# Main.net
KiCad netlist of a schematic drawn in Altium Designer
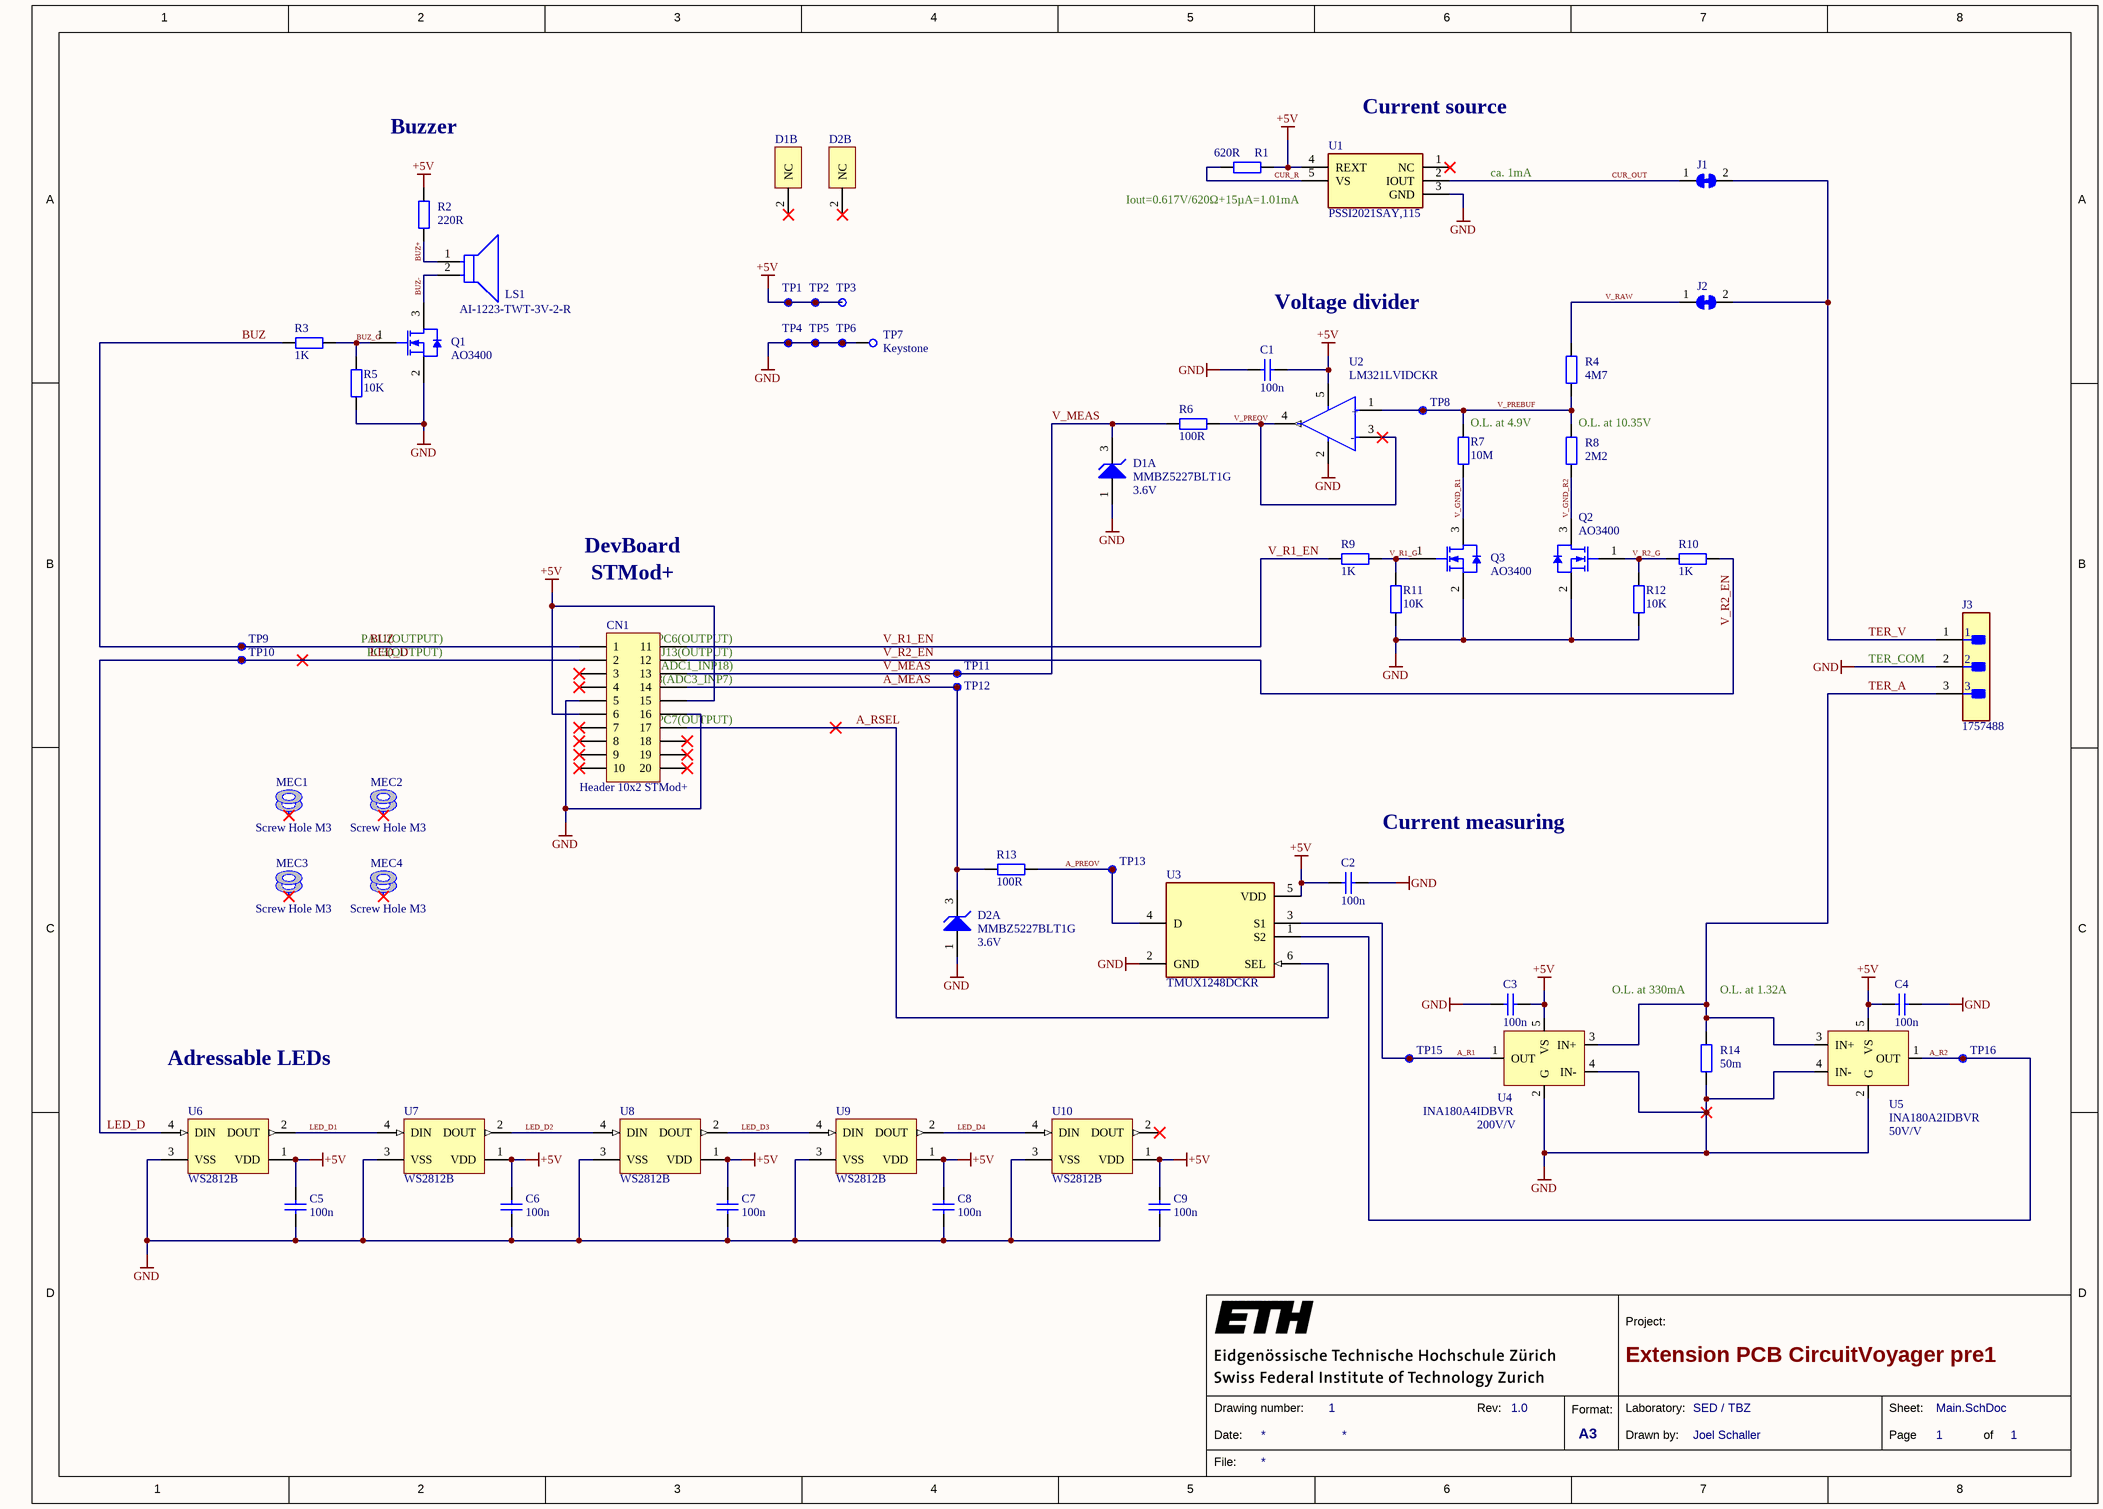
[diagram p0: Main.SchDoc]

(export (version "E")
  (design (tool "Eeschema 10.0.6"))
  (components
    (comp (ref "C1")
      (value "100n")
      (footprint "SMD_CAPC1005X06N")
      (description "CERCAP 100n 16V 5% X7R 0402")
      (fields
        (field (name "MANUFACTURER") "KEMET")
        (field (name "MANUFACTURER PART NUMBER") "C0402C104J4RAC7867")
      )
      (libsource (lib "ETHZ Vault") (part "Cap"))
    )
    (comp (ref "C2")
      (value "100n")
      (footprint "SMD_CAPC1005X06N")
      (description "CERCAP 100n 16V 5% X7R 0402")
      (fields
        (field (name "MANUFACTURER") "KEMET")
        (field (name "MANUFACTURER PART NUMBER") "C0402C104J4RAC7867")
      )
      (libsource (lib "ETHZ Vault") (part "Cap"))
    )
    (comp (ref "C3")
      (value "100n")
      (footprint "SMD_CAPC1005X06N")
      (description "CERCAP 100n 16V 5% X7R 0402")
      (fields
        (field (name "MANUFACTURER") "KEMET")
        (field (name "MANUFACTURER PART NUMBER") "C0402C104J4RAC7867")
      )
      (libsource (lib "ETHZ Vault") (part "Cap"))
    )
    (comp (ref "C4")
      (value "100n")
      (footprint "SMD_CAPC1005X06N")
      (description "CERCAP 100n 16V 5% X7R 0402")
      (fields
        (field (name "MANUFACTURER") "KEMET")
        (field (name "MANUFACTURER PART NUMBER") "C0402C104J4RAC7867")
      )
      (libsource (lib "ETHZ Vault") (part "Cap"))
    )
    (comp (ref "C5")
      (value "100n")
      (footprint "SMD_CAPC1005X06N")
      (description "CERCAP 100n 16V 5% X7R 0402")
      (fields
        (field (name "MANUFACTURER") "KEMET")
        (field (name "MANUFACTURER PART NUMBER") "C0402C104J4RAC7867")
      )
      (libsource (lib "ETHZ Vault") (part "Cap"))
    )
    (comp (ref "C6")
      (value "100n")
      (footprint "SMD_CAPC1005X06N")
      (description "CERCAP 100n 16V 5% X7R 0402")
      (fields
        (field (name "MANUFACTURER") "KEMET")
        (field (name "MANUFACTURER PART NUMBER") "C0402C104J4RAC7867")
      )
      (libsource (lib "ETHZ Vault") (part "Cap"))
    )
    (comp (ref "C7")
      (value "100n")
      (footprint "SMD_CAPC1005X06N")
      (description "CERCAP 100n 16V 5% X7R 0402")
      (fields
        (field (name "MANUFACTURER") "KEMET")
        (field (name "MANUFACTURER PART NUMBER") "C0402C104J4RAC7867")
      )
      (libsource (lib "ETHZ Vault") (part "Cap"))
    )
    (comp (ref "C8")
      (value "100n")
      (footprint "SMD_CAPC1005X06N")
      (description "CERCAP 100n 16V 5% X7R 0402")
      (fields
        (field (name "MANUFACTURER") "KEMET")
        (field (name "MANUFACTURER PART NUMBER") "C0402C104J4RAC7867")
      )
      (libsource (lib "ETHZ Vault") (part "Cap"))
    )
    (comp (ref "C9")
      (value "100n")
      (footprint "SMD_CAPC1005X06N")
      (description "CERCAP 100n 16V 5% X7R 0402")
      (fields
        (field (name "MANUFACTURER") "KEMET")
        (field (name "MANUFACTURER PART NUMBER") "C0402C104J4RAC7867")
      )
      (libsource (lib "ETHZ Vault") (part "Cap"))
    )
    (comp (ref "CN1")
      (value "Header 10x2 STMod+")
      (footprint "MB1280:CON_SAMTEC_TMM-110-01-L-D-RA__STMOD+")
      (description "Header 10x2, 2mm, RA, TH, Height 3.20mm/3.50mm,BF060-20A-B-0400-0280-0305-L-D")
      (fields
        (field (name "INTERNAL_PART_NUMBER") "MCD-00288")
        (field (name "MANUFACTURER_PART_NUMBER") "TMM-110-01-L-D-RA")
        (field (name "PROVIDED_BY") "SUBCO")
      )
      (libsource (lib "MCD_PARTS_database") (part "Header 10x2 STMod+"))
    )
    (comp (ref "D1")
      (value "MMBZ5227BLT1G")
      (footprint "ONSC-SOT-23-3-318-08_V")
      (description "Zener Voltage Regulator, 225 mW, 3-Pin SOT-23, Pb-Free, Tape and Reel")
      (fields (field (name "VZ TYP (V)") "3.6V") (field (name "MANUFACTURER") "On Semiconductor"))
      (libsource (lib "Altium Content Vault") (part "ONSC-A1K3-3"))
    )
    (comp (ref "D2")
      (value "MMBZ5227BLT1G")
      (footprint "ONSC-SOT-23-3-318-08_V")
      (description "Zener Voltage Regulator, 225 mW, 3-Pin SOT-23, Pb-Free, Tape and Reel")
      (fields (field (name "VZ TYP (V)") "3.6V") (field (name "MANUFACTURER") "On Semiconductor"))
      (libsource (lib "Altium Content Vault") (part "ONSC-A1K3-3"))
    )
    (comp (ref "J1")
      (value "SOLDERJUMPER_CLOSED_1MM")
      (footprint "SOLDERBRIDGE_CLOSED_1MM")
      (description "TP SOLDERJUMPER CLOSED 1mm")
      (libsource (lib "ETHZ Vault") (part "CON SOLDER JUMPER CLOSED"))
    )
    (comp (ref "J2")
      (value "SOLDERJUMPER_CLOSED_1MM")
      (footprint "SOLDERBRIDGE_CLOSED_1MM")
      (description "TP SOLDERJUMPER CLOSED 1mm")
      (libsource (lib "ETHZ Vault") (part "CON SOLDER JUMPER CLOSED"))
    )
    (comp (ref "J3")
      (value "1757488")
      (footprint "FP-1757488-MFG")
      (description "TERM BLOCK HDR 3POS 90DEG 5MM")
      (fields
        (field (name "OCTOPART") "https://octopart.com/1757488-phoenix+contact-37691")
        (field (name "MANUFACTURER") "Phoenix Contact")
      )
      (libsource (lib "Altium Content Vault") (part "0d3f023dd272f625e17a2be33dea85f"))
    )
    (comp (ref "LS1")
      (value "AI-1223-TWT-3V-2-R")
      (footprint "FP-AI-1223-TWT-3V-2-R-MFG")
      (description "BUZZER MAGNETIC 3V 12MM TH")
      (libsource (lib "Altium Content Vault") (part "1973c4b650225fd2ddacaff6b763965"))
    )
    (comp (ref "MEC1")
      (value "Screw Hole M3")
      (footprint "Screw M3 ISO 7380-1")
      (description "EMECH Generic Screw Hole - different sizes")
      (libsource (lib "ETHZ Vault") (part "Generic Screw Hole"))
    )
    (comp (ref "MEC2")
      (value "Screw Hole M3")
      (footprint "Screw M3 ISO 7380-1")
      (description "EMECH Generic Screw Hole - different sizes")
      (libsource (lib "ETHZ Vault") (part "Generic Screw Hole"))
    )
    (comp (ref "MEC3")
      (value "Screw Hole M3")
      (footprint "Screw M3 ISO 7380-1")
      (description "EMECH Generic Screw Hole - different sizes")
      (libsource (lib "ETHZ Vault") (part "Generic Screw Hole"))
    )
    (comp (ref "MEC4")
      (value "Screw Hole M3")
      (footprint "Screw M3 ISO 7380-1")
      (description "EMECH Generic Screw Hole - different sizes")
      (libsource (lib "ETHZ Vault") (part "Generic Screw Hole"))
    )
    (comp (ref "Q1")
      (value "AO3400")
      (footprint "AO-SOT23-3_V")
      (description "N-channel Enhancement Mode Field-Effect Transistor; 5.8A/30V")
      (fields (field (name "MANUFACTURER") "Alpha and Omega"))
      (libsource (lib "Altium Content Vault") (part "AO-NEMOS-G1S2D3-3"))
    )
    (comp (ref "Q2")
      (value "AO3400")
      (footprint "AO-SOT23-3_V")
      (description "N-channel Enhancement Mode Field-Effect Transistor; 5.8A/30V")
      (fields (field (name "MANUFACTURER") "Alpha and Omega"))
      (libsource (lib "Altium Content Vault") (part "AO-NEMOS-G1S2D3-3"))
    )
    (comp (ref "Q3")
      (value "AO3400")
      (footprint "AO-SOT23-3_V")
      (description "N-channel Enhancement Mode Field-Effect Transistor; 5.8A/30V")
      (fields (field (name "MANUFACTURER") "Alpha and Omega"))
      (libsource (lib "Altium Content Vault") (part "AO-NEMOS-G1S2D3-3"))
    )
    (comp (ref "R1")
      (value "620R")
      (footprint "SMD_RESC1005X04N")
      (description "RES 620R 62.5mW 1% 0402")
      (fields
        (field (name "MANUFACTURER") "YAEGO")
        (field (name "MANUFACTURER PART NUMBER") "RC0402FR-07620RL")
      )
      (libsource (lib "ETHZ Vault") (part "Res"))
    )
    (comp (ref "R2")
      (value "220R")
      (footprint "SMD_RESC1005X04N")
      (description "RES 220R 62.5mW 1% 0402")
      (fields
        (field (name "MANUFACTURER") "YAEGO")
        (field (name "MANUFACTURER PART NUMBER") "RC0402FR-07220RL")
      )
      (libsource (lib "ETHZ Vault") (part "Res"))
    )
    (comp (ref "R3")
      (value "1K")
      (footprint "SMD_RESC1005X04N")
      (description "RES 1K 62.5mW 1% 0402")
      (fields
        (field (name "MANUFACTURER") "YAEGO")
        (field (name "MANUFACTURER PART NUMBER") "RC0402FR-071KL")
      )
      (libsource (lib "ETHZ Vault") (part "Res"))
    )
    (comp (ref "R4")
      (value "4M7")
      (footprint "SMD_RESC1005X04N")
      (description "RES 4M7 62.5mW 1% 0402")
      (fields
        (field (name "MANUFACTURER") "YAEGO")
        (field (name "MANUFACTURER PART NUMBER") "RC0402FR-074M7L")
      )
      (libsource (lib "ETHZ Vault") (part "Res"))
    )
    (comp (ref "R5")
      (value "10K")
      (footprint "SMD_RESC1005X04N")
      (description "RES 10K 62.5mW 1% 0402")
      (fields
        (field (name "MANUFACTURER") "YAEGO")
        (field (name "MANUFACTURER PART NUMBER") "RC0402FR-0710KL")
      )
      (libsource (lib "ETHZ Vault") (part "Res"))
    )
    (comp (ref "R6")
      (value "100R")
      (footprint "SMD_RESC1005X04N")
      (description "RES 100R 62.5mW 1% 0402")
      (fields
        (field (name "MANUFACTURER") "YAEGO")
        (field (name "MANUFACTURER PART NUMBER") "RC0402FR-07100RL")
      )
      (libsource (lib "ETHZ Vault") (part "Res"))
    )
    (comp (ref "R7")
      (value "10M")
      (footprint "SMD_RESC1005X04N")
      (description "RES 10M 62.5mW 1% 0402")
      (fields
        (field (name "MANUFACTURER") "YAEGO")
        (field (name "MANUFACTURER PART NUMBER") "RC0402FR-0710ML")
      )
      (libsource (lib "ETHZ Vault") (part "Res"))
    )
    (comp (ref "R8")
      (value "2M2")
      (footprint "SMD_RESC1005X04N")
      (description "RES 2M2 62.5mW 1% 0402")
      (fields
        (field (name "MANUFACTURER") "YAEGO")
        (field (name "MANUFACTURER PART NUMBER") "RC0402FR-072M2L")
      )
      (libsource (lib "ETHZ Vault") (part "Res"))
    )
    (comp (ref "R9")
      (value "1K")
      (footprint "SMD_RESC1005X04N")
      (description "RES 1K 62.5mW 1% 0402")
      (fields
        (field (name "MANUFACTURER") "YAEGO")
        (field (name "MANUFACTURER PART NUMBER") "RC0402FR-071KL")
      )
      (libsource (lib "ETHZ Vault") (part "Res"))
    )
    (comp (ref "R10")
      (value "1K")
      (footprint "SMD_RESC1005X04N")
      (description "RES 1K 62.5mW 1% 0402")
      (fields
        (field (name "MANUFACTURER") "YAEGO")
        (field (name "MANUFACTURER PART NUMBER") "RC0402FR-071KL")
      )
      (libsource (lib "ETHZ Vault") (part "Res"))
    )
    (comp (ref "R11")
      (value "10K")
      (footprint "SMD_RESC1005X04N")
      (description "RES 10K 62.5mW 1% 0402")
      (fields
        (field (name "MANUFACTURER") "YAEGO")
        (field (name "MANUFACTURER PART NUMBER") "RC0402FR-0710KL")
      )
      (libsource (lib "ETHZ Vault") (part "Res"))
    )
    (comp (ref "R12")
      (value "10K")
      (footprint "SMD_RESC1005X04N")
      (description "RES 10K 62.5mW 1% 0402")
      (fields
        (field (name "MANUFACTURER") "YAEGO")
        (field (name "MANUFACTURER PART NUMBER") "RC0402FR-0710KL")
      )
      (libsource (lib "ETHZ Vault") (part "Res"))
    )
    (comp (ref "R13")
      (value "100R")
      (footprint "SMD_RESC1005X04N")
      (description "RES 100R 62.5mW 1% 0402")
      (fields
        (field (name "MANUFACTURER") "YAEGO")
        (field (name "MANUFACTURER PART NUMBER") "RC0402FR-07100RL")
      )
      (libsource (lib "ETHZ Vault") (part "Res"))
    )
    (comp (ref "R14")
      (value "50m")
      (footprint "SMD_RESC2012X05N")
      (description "RES 0R05 125mW 1% 0805")
      (fields (field (name "Comment") "R0805"))
      (libsource (lib "ETHZ Vault") (part "Res"))
    )
    (comp (ref "TP1")
      (value "Test Point Small")
      (footprint "SMD_PAD_1mm")
      (description "TP TESTPOINT MULTIPLE_SIZE")
      (libsource (lib "ETHZ Vault") (part "Test Point Small"))
    )
    (comp (ref "TP2")
      (value "Test Point Small")
      (footprint "SMD_PAD_1mm")
      (description "TP TESTPOINT MULTIPLE_SIZE")
      (libsource (lib "ETHZ Vault") (part "Test Point Small"))
    )
    (comp (ref "TP3")
      (value "Test Point Small")
      (footprint "SMD_PAD_1mm")
      (description "TP TESTPOINT MULTIPLE_SIZE")
      (libsource (lib "ETHZ Vault") (part "Test Point Small"))
    )
    (comp (ref "TP4")
      (value "Test Point Small")
      (footprint "SMD_PAD_1mm")
      (description "TP TESTPOINT MULTIPLE_SIZE")
      (libsource (lib "ETHZ Vault") (part "Test Point Small"))
    )
    (comp (ref "TP5")
      (value "Test Point Small")
      (footprint "SMD_PAD_1mm")
      (description "TP TESTPOINT MULTIPLE_SIZE")
      (libsource (lib "ETHZ Vault") (part "Test Point Small"))
    )
    (comp (ref "TP6")
      (value "Test Point Small")
      (footprint "SMD_PAD_1mm")
      (description "TP TESTPOINT MULTIPLE_SIZE")
      (libsource (lib "ETHZ Vault") (part "Test Point Small"))
    )
    (comp (ref "TP7")
      (value "Keystone")
      (footprint "KEYSTONE_5019")
      (description "TP SMD 3.81x 2.03mm")
      (fields
        (field (name "MANUFACTURER") "Keystone Electronics")
        (field (name "MANUFACTURER PART NUMBER") "5019")
      )
      (libsource (lib "ETHZ Vault") (part "Test Point"))
    )
    (comp (ref "TP8")
      (value "Test Point Small")
      (footprint "SMD_PAD_1mm")
      (description "TP TESTPOINT MULTIPLE_SIZE")
      (libsource (lib "ETHZ Vault") (part "Test Point Small"))
    )
    (comp (ref "TP9")
      (value "Test Point Small")
      (footprint "SMD_PAD_1mm")
      (description "TP TESTPOINT MULTIPLE_SIZE")
      (libsource (lib "ETHZ Vault") (part "Test Point Small"))
    )
    (comp (ref "TP10")
      (value "Test Point Small")
      (footprint "SMD_PAD_1mm")
      (description "TP TESTPOINT MULTIPLE_SIZE")
      (libsource (lib "ETHZ Vault") (part "Test Point Small"))
    )
    (comp (ref "TP11")
      (value "Test Point Small")
      (footprint "SMD_PAD_1mm")
      (description "TP TESTPOINT MULTIPLE_SIZE")
      (libsource (lib "ETHZ Vault") (part "Test Point Small"))
    )
    (comp (ref "TP12")
      (value "Test Point Small")
      (footprint "SMD_PAD_1mm")
      (description "TP TESTPOINT MULTIPLE_SIZE")
      (libsource (lib "ETHZ Vault") (part "Test Point Small"))
    )
    (comp (ref "TP13")
      (value "Test Point Small")
      (footprint "SMD_PAD_1mm")
      (description "TP TESTPOINT MULTIPLE_SIZE")
      (libsource (lib "ETHZ Vault") (part "Test Point Small"))
    )
    (comp (ref "TP15")
      (value "Test Point Small")
      (footprint "SMD_PAD_1mm")
      (description "TP TESTPOINT MULTIPLE_SIZE")
      (libsource (lib "ETHZ Vault") (part "Test Point Small"))
    )
    (comp (ref "TP16")
      (value "Test Point Small")
      (footprint "SMD_PAD_1mm")
      (description "TP TESTPOINT MULTIPLE_SIZE")
      (libsource (lib "ETHZ Vault") (part "Test Point Small"))
    )
    (comp (ref "U1")
      (value "PSSI2021SAY,115")
      (footprint "SOT65P210X100-5N:SOT65P210X100-5N")
      (description "NEXPERIA - PSSI2021SAY,115 - IC, CURRENT SOURCE, 50MA, 75V,SOT353")
      (fields (field (name "MOUSER PART NUMBER") "771-PSSI2021SAY-T/R"))
      (libsource (lib "PSSI2021SAY_115") (part "PSSI2021SAY_115"))
    )
    (comp (ref "U2")
      (value "LM321LVIDCKR")
      (footprint "FP-DCK0005A-IPC_B")
      (description "IC OPAMP GP 1 CIRCUIT SC70-5")
      (libsource (lib "Altium Content Vault") (part "471d8b929410cd356ad4b122f572ce5"))
    )
    (comp (ref "U3")
      (value "TMUX1248DCKR")
      (footprint "FP-DCK0006A-IPC_B")
      (description "3- LOW RON, 5-V, 2:1 (SPDT) GENE")
      (libsource (lib "Altium Content Vault") (part "a68f7588cd528286686894cb26da2a0"))
    )
    (comp (ref "U4")
      (value "INA180A4IDBVR")
      (footprint "FP-DBV0005A-IPC_B")
      (description "Operational Amplifier, 1 Func, 500uV Offset-Max, PDSO5")
      (fields (field (name "ALTIUM_VALUE") "200V/V"))
      (libsource (lib "Joel's WS") (part "0a55cf1a948ad01a3239aec1b7efad0"))
    )
    (comp (ref "U5")
      (value "INA180A2IDBVR")
      (footprint "FP-DBV0005A-IPC_B")
      (description "Operational Amplifier, 1 Func, 500uV Offset-Max, PDSO5")
      (fields (field (name "ALTIUM_VALUE") "50V/V"))
      (libsource (lib "") (part "0a55cf1a948ad01a3239aec1b7efad0_1"))
    )
    (comp (ref "U6")
      (value "WS2812B")
      (footprint "ADAI-WS2812B_V")
      (fields (field (name "MANUFACTURER") "Adafruit Industries"))
      (libsource (lib "ETH Zürich") (part "ADAI-WS2812B-4"))
    )
    (comp (ref "U7")
      (value "WS2812B")
      (footprint "ADAI-WS2812B_V")
      (fields (field (name "MANUFACTURER") "Adafruit Industries"))
      (libsource (lib "ETH Zürich") (part "ADAI-WS2812B-4"))
    )
    (comp (ref "U8")
      (value "WS2812B")
      (footprint "ADAI-WS2812B_V")
      (fields (field (name "MANUFACTURER") "Adafruit Industries"))
      (libsource (lib "ETH Zürich") (part "ADAI-WS2812B-4"))
    )
    (comp (ref "U9")
      (value "WS2812B")
      (footprint "ADAI-WS2812B_V")
      (fields (field (name "MANUFACTURER") "Adafruit Industries"))
      (libsource (lib "ETH Zürich") (part "ADAI-WS2812B-4"))
    )
    (comp (ref "U10")
      (value "WS2812B")
      (footprint "ADAI-WS2812B_V")
      (fields (field (name "MANUFACTURER") "Adafruit Industries"))
      (libsource (lib "ETH Zürich") (part "ADAI-WS2812B-4"))
    )
  )
  (nets
    (net (code "1") (name "+5V") (class "Default")
      (node (ref "C1") (pin "1") (pinfunction "1_1") (pintype "passive"))
      (node (ref "C2") (pin "1") (pinfunction "1_1") (pintype "passive"))
      (node (ref "C3") (pin "1") (pinfunction "1_1") (pintype "passive"))
      (node (ref "C4") (pin "1") (pinfunction "1_1") (pintype "passive"))
      (node (ref "C5") (pin "2") (pinfunction "2_2") (pintype "passive"))
      (node (ref "C6") (pin "2") (pinfunction "2_2") (pintype "passive"))
      (node (ref "C7") (pin "2") (pinfunction "2_2") (pintype "passive"))
      (node (ref "C8") (pin "2") (pinfunction "2_2") (pintype "passive"))
      (node (ref "C9") (pin "2") (pinfunction "2_2") (pintype "passive"))
      (node (ref "CN1") (pin "15") (pinfunction "15_15") (pintype "passive"))
      (node (ref "CN1") (pin "6") (pinfunction "6_6") (pintype "passive"))
      (node (ref "R1") (pin "1") (pinfunction "1_1") (pintype "passive"))
      (node (ref "R2") (pin "2") (pinfunction "2_2") (pintype "passive"))
      (node (ref "TP1") (pin "1") (pinfunction "1_1") (pintype "passive"))
      (node (ref "TP2") (pin "1") (pinfunction "1_1") (pintype "passive"))
      (node (ref "TP3") (pin "1") (pinfunction "1_1") (pintype "passive"))
      (node (ref "U1") (pin "4") (pinfunction "REXT_4") (pintype "passive"))
      (node (ref "U10") (pin "1") (pinfunction "VDD_1") (pintype "power_in"))
      (node (ref "U2") (pin "5") (pinfunction "V+_5") (pintype "power_in"))
      (node (ref "U3") (pin "5") (pinfunction "VDD_5") (pintype "power_in"))
      (node (ref "U4") (pin "5") (pinfunction "VS_5") (pintype "power_in"))
      (node (ref "U5") (pin "5") (pinfunction "VS_5") (pintype "power_in"))
      (node (ref "U6") (pin "1") (pinfunction "VDD_1") (pintype "power_in"))
      (node (ref "U7") (pin "1") (pinfunction "VDD_1") (pintype "power_in"))
      (node (ref "U8") (pin "1") (pinfunction "VDD_1") (pintype "power_in"))
      (node (ref "U9") (pin "1") (pinfunction "VDD_1") (pintype "power_in"))
    )
    (net (code "2") (name "/A_MEAS") (class "Default")
      (node (ref "CN1") (pin "14") (pinfunction "14_14") (pintype "passive"))
      (node (ref "D2") (pin "3") (pinfunction "K_3") (pintype "passive"))
      (node (ref "R13") (pin "1") (pinfunction "1_1") (pintype "passive"))
      (node (ref "TP12") (pin "1") (pinfunction "1_1") (pintype "passive"))
    )
    (net (code "3") (name "/A_PREOV") (class "Default")
      (node (ref "R13") (pin "2") (pinfunction "2_2") (pintype "passive"))
      (node (ref "TP13") (pin "1") (pinfunction "1_1") (pintype "passive"))
      (node (ref "U3") (pin "4") (pinfunction "D_4") (pintype "passive"))
    )
    (net (code "4") (name "/A_R1") (class "Default")
      (node (ref "TP15") (pin "1") (pinfunction "1_1") (pintype "passive"))
      (node (ref "U3") (pin "3") (pinfunction "S1_3") (pintype "passive"))
      (node (ref "U4") (pin "1") (pinfunction "OUT_1") (pintype "passive"))
    )
    (net (code "5") (name "/A_R2") (class "Default")
      (node (ref "TP16") (pin "1") (pinfunction "1_1") (pintype "passive"))
      (node (ref "U3") (pin "1") (pinfunction "S2_1") (pintype "passive"))
      (node (ref "U5") (pin "1") (pinfunction "OUT_1") (pintype "passive"))
    )
    (net (code "6") (name "/A_RSEL") (class "Default")
      (node (ref "CN1") (pin "17") (pinfunction "17_17") (pintype "passive"))
      (node (ref "U3") (pin "6") (pinfunction "SEL_6") (pintype "input"))
    )
    (net (code "7") (name "/BUZ") (class "Default")
      (node (ref "CN1") (pin "1") (pinfunction "1_1") (pintype "passive"))
      (node (ref "R3") (pin "2") (pinfunction "2_2") (pintype "passive"))
      (node (ref "TP9") (pin "1") (pinfunction "1_1") (pintype "passive"))
    )
    (net (code "8") (name "/BUZ+") (class "Default")
      (node (ref "LS1") (pin "1") (pinfunction "C_1") (pintype "passive"))
      (node (ref "R2") (pin "1") (pinfunction "1_1") (pintype "passive"))
    )
    (net (code "9") (name "/BUZ-") (class "Default")
      (node (ref "LS1") (pin "2") (pinfunction "A_2") (pintype "passive"))
      (node (ref "Q1") (pin "3") (pinfunction "D_3") (pintype "passive"))
    )
    (net (code "10") (name "/BUZ_G") (class "Default")
      (node (ref "Q1") (pin "1") (pinfunction "G_1") (pintype "passive"))
      (node (ref "R3") (pin "1") (pinfunction "1_1") (pintype "passive"))
      (node (ref "R5") (pin "2") (pinfunction "2_2") (pintype "passive"))
    )
    (net (code "11") (name "/CUR_OUT") (class "Default")
      (node (ref "J1") (pin "1") (pinfunction "1_1") (pintype "passive"))
      (node (ref "U1") (pin "2") (pinfunction "IOUT_2") (pintype "passive"))
    )
    (net (code "12") (name "/CUR_R") (class "Default")
      (node (ref "R1") (pin "2") (pinfunction "2_2") (pintype "passive"))
      (node (ref "U1") (pin "5") (pinfunction "VS_5") (pintype "power_in"))
    )
    (net (code "13") (name "/LED_D") (class "Default")
      (node (ref "CN1") (pin "2") (pinfunction "2_2") (pintype "passive"))
      (node (ref "TP10") (pin "1") (pinfunction "1_1") (pintype "passive"))
      (node (ref "U6") (pin "4") (pinfunction "DIN_4") (pintype "input"))
    )
    (net (code "14") (name "/LED_D1") (class "Default")
      (node (ref "U6") (pin "2") (pinfunction "DOUT_2") (pintype "output"))
      (node (ref "U7") (pin "4") (pinfunction "DIN_4") (pintype "input"))
    )
    (net (code "15") (name "/LED_D2") (class "Default")
      (node (ref "U7") (pin "2") (pinfunction "DOUT_2") (pintype "output"))
      (node (ref "U8") (pin "4") (pinfunction "DIN_4") (pintype "input"))
    )
    (net (code "16") (name "/LED_D3") (class "Default")
      (node (ref "U8") (pin "2") (pinfunction "DOUT_2") (pintype "output"))
      (node (ref "U9") (pin "4") (pinfunction "DIN_4") (pintype "input"))
    )
    (net (code "17") (name "/LED_D4") (class "Default")
      (node (ref "U10") (pin "4") (pinfunction "DIN_4") (pintype "input"))
      (node (ref "U9") (pin "2") (pinfunction "DOUT_2") (pintype "output"))
    )
    (net (code "18") (name "/TER_A") (class "Default")
      (node (ref "J3") (pin "3") (pinfunction "3_3") (pintype "passive"))
      (node (ref "R14") (pin "2") (pinfunction "2_2") (pintype "passive"))
      (node (ref "U4") (pin "3") (pinfunction "IN+_3") (pintype "tri_state"))
      (node (ref "U5") (pin "3") (pinfunction "IN+_3") (pintype "tri_state"))
    )
    (net (code "19") (name "/TER_V") (class "Default")
      (node (ref "J1") (pin "2") (pinfunction "2_2") (pintype "passive"))
      (node (ref "J2") (pin "2") (pinfunction "2_2") (pintype "passive"))
      (node (ref "J3") (pin "1") (pinfunction "1_1") (pintype "passive"))
    )
    (net (code "20") (name "/V_GND_R1") (class "Default")
      (node (ref "Q3") (pin "3") (pinfunction "D_3") (pintype "passive"))
      (node (ref "R7") (pin "1") (pinfunction "1_1") (pintype "passive"))
    )
    (net (code "21") (name "/V_GND_R2") (class "Default")
      (node (ref "Q2") (pin "3") (pinfunction "D_3") (pintype "passive"))
      (node (ref "R8") (pin "1") (pinfunction "1_1") (pintype "passive"))
    )
    (net (code "22") (name "/V_MEAS") (class "Default")
      (node (ref "CN1") (pin "13") (pinfunction "13_13") (pintype "passive"))
      (node (ref "D1") (pin "3") (pinfunction "K_3") (pintype "passive"))
      (node (ref "R6") (pin "1") (pinfunction "1_1") (pintype "passive"))
      (node (ref "TP11") (pin "1") (pinfunction "1_1") (pintype "passive"))
    )
    (net (code "23") (name "/V_PREBUF") (class "Default")
      (node (ref "R4") (pin "1") (pinfunction "1_1") (pintype "passive"))
      (node (ref "R7") (pin "2") (pinfunction "2_2") (pintype "passive"))
      (node (ref "R8") (pin "2") (pinfunction "2_2") (pintype "passive"))
      (node (ref "TP8") (pin "1") (pinfunction "1_1") (pintype "passive"))
      (node (ref "U2") (pin "1") (pinfunction "IN+_1") (pintype "tri_state"))
    )
    (net (code "24") (name "/V_PREOV") (class "Default")
      (node (ref "R6") (pin "2") (pinfunction "2_2") (pintype "passive"))
      (node (ref "U2") (pin "3") (pinfunction "IN-_3") (pintype "tri_state"))
      (node (ref "U2") (pin "4") (pinfunction "OUT_4") (pintype "output"))
    )
    (net (code "25") (name "/V_R1_EN") (class "Default")
      (node (ref "CN1") (pin "11") (pinfunction "11_11") (pintype "passive"))
      (node (ref "R9") (pin "2") (pinfunction "2_2") (pintype "passive"))
    )
    (net (code "26") (name "/V_R1_G") (class "Default")
      (node (ref "Q3") (pin "1") (pinfunction "G_1") (pintype "passive"))
      (node (ref "R11") (pin "2") (pinfunction "2_2") (pintype "passive"))
      (node (ref "R9") (pin "1") (pinfunction "1_1") (pintype "passive"))
    )
    (net (code "27") (name "/V_R2_EN") (class "Default")
      (node (ref "CN1") (pin "12") (pinfunction "12_12") (pintype "passive"))
      (node (ref "R10") (pin "2") (pinfunction "2_2") (pintype "passive"))
    )
    (net (code "28") (name "/V_R2_G") (class "Default")
      (node (ref "Q2") (pin "1") (pinfunction "G_1") (pintype "passive"))
      (node (ref "R10") (pin "1") (pinfunction "1_1") (pintype "passive"))
      (node (ref "R12") (pin "2") (pinfunction "2_2") (pintype "passive"))
    )
    (net (code "29") (name "/V_RAW") (class "Default")
      (node (ref "J2") (pin "1") (pinfunction "1_1") (pintype "passive"))
      (node (ref "R4") (pin "2") (pinfunction "2_2") (pintype "passive"))
    )
    (net (code "30") (name "GND") (class "Default")
      (node (ref "C1") (pin "2") (pinfunction "2_2") (pintype "passive"))
      (node (ref "C2") (pin "2") (pinfunction "2_2") (pintype "passive"))
      (node (ref "C3") (pin "2") (pinfunction "2_2") (pintype "passive"))
      (node (ref "C4") (pin "2") (pinfunction "2_2") (pintype "passive"))
      (node (ref "C5") (pin "1") (pinfunction "1_1") (pintype "passive"))
      (node (ref "C6") (pin "1") (pinfunction "1_1") (pintype "passive"))
      (node (ref "C7") (pin "1") (pinfunction "1_1") (pintype "passive"))
      (node (ref "C8") (pin "1") (pinfunction "1_1") (pintype "passive"))
      (node (ref "C9") (pin "1") (pinfunction "1_1") (pintype "passive"))
      (node (ref "CN1") (pin "16") (pinfunction "16_16") (pintype "passive"))
      (node (ref "CN1") (pin "5") (pinfunction "5_5") (pintype "passive"))
      (node (ref "D1") (pin "1") (pinfunction "A_1") (pintype "passive"))
      (node (ref "D2") (pin "1") (pinfunction "A_1") (pintype "passive"))
      (node (ref "J3") (pin "2") (pinfunction "2_2") (pintype "passive"))
      (node (ref "Q1") (pin "2") (pinfunction "S_2") (pintype "passive"))
      (node (ref "Q2") (pin "2") (pinfunction "S_2") (pintype "passive"))
      (node (ref "Q3") (pin "2") (pinfunction "S_2") (pintype "passive"))
      (node (ref "R11") (pin "1") (pinfunction "1_1") (pintype "passive"))
      (node (ref "R12") (pin "1") (pinfunction "1_1") (pintype "passive"))
      (node (ref "R14") (pin "1") (pinfunction "1_1") (pintype "passive"))
      (node (ref "R5") (pin "1") (pinfunction "1_1") (pintype "passive"))
      (node (ref "TP4") (pin "1") (pinfunction "1_1") (pintype "passive"))
      (node (ref "TP5") (pin "1") (pinfunction "1_1") (pintype "passive"))
      (node (ref "TP6") (pin "1") (pinfunction "1_1") (pintype "passive"))
      (node (ref "TP7") (pin "1") (pinfunction "1_1") (pintype "passive"))
      (node (ref "U1") (pin "3") (pinfunction "GND_3") (pintype "passive"))
      (node (ref "U10") (pin "3") (pinfunction "VSS_3") (pintype "power_in"))
      (node (ref "U2") (pin "2") (pinfunction "V-_2") (pintype "power_in"))
      (node (ref "U3") (pin "2") (pinfunction "GND_2") (pintype "power_in"))
      (node (ref "U4") (pin "2") (pinfunction "G_2") (pintype "power_in"))
      (node (ref "U4") (pin "4") (pinfunction "IN-_4") (pintype "tri_state"))
      (node (ref "U5") (pin "2") (pinfunction "G_2") (pintype "power_in"))
      (node (ref "U5") (pin "4") (pinfunction "IN-_4") (pintype "tri_state"))
      (node (ref "U6") (pin "3") (pinfunction "VSS_3") (pintype "power_in"))
      (node (ref "U7") (pin "3") (pinfunction "VSS_3") (pintype "power_in"))
      (node (ref "U8") (pin "3") (pinfunction "VSS_3") (pintype "power_in"))
      (node (ref "U9") (pin "3") (pinfunction "VSS_3") (pintype "power_in"))
    )
    (net (code "31") (name "unconnected-(CN1-Pad3)") (class "Default")
      (node (ref "CN1") (pin "3") (pinfunction "3_3") (pintype "passive+no_connect"))
    )
    (net (code "32") (name "unconnected-(CN1-Pad4)") (class "Default")
      (node (ref "CN1") (pin "4") (pinfunction "4_4") (pintype "passive+no_connect"))
    )
    (net (code "33") (name "unconnected-(CN1-Pad7)") (class "Default")
      (node (ref "CN1") (pin "7") (pinfunction "7_7") (pintype "passive+no_connect"))
    )
    (net (code "34") (name "unconnected-(CN1-Pad8)") (class "Default")
      (node (ref "CN1") (pin "8") (pinfunction "8_8") (pintype "passive+no_connect"))
    )
    (net (code "35") (name "unconnected-(CN1-Pad9)") (class "Default")
      (node (ref "CN1") (pin "9") (pinfunction "9_9") (pintype "passive+no_connect"))
    )
    (net (code "36") (name "unconnected-(CN1-Pad10)") (class "Default")
      (node (ref "CN1") (pin "10") (pinfunction "10_10") (pintype "passive+no_connect"))
    )
    (net (code "37") (name "unconnected-(CN1-Pad18)") (class "Default")
      (node (ref "CN1") (pin "18") (pinfunction "18_18") (pintype "passive+no_connect"))
    )
    (net (code "38") (name "unconnected-(CN1-Pad19)") (class "Default")
      (node (ref "CN1") (pin "19") (pinfunction "19_19") (pintype "passive+no_connect"))
    )
    (net (code "39") (name "unconnected-(CN1-Pad20)") (class "Default")
      (node (ref "CN1") (pin "20") (pinfunction "20_20") (pintype "passive+no_connect"))
    )
    (net (code "40") (name "unconnected-(D1B-NC-Pad2)") (class "Default")
      (node (ref "D1") (pin "2") (pinfunction "NC_2") (pintype "passive+no_connect"))
    )
    (net (code "41") (name "unconnected-(D2B-NC-Pad2)") (class "Default")
      (node (ref "D2") (pin "2") (pinfunction "NC_2") (pintype "passive+no_connect"))
    )
    (net (code "42") (name "unconnected-(MEC1-2-Pad1)") (class "Default")
      (node (ref "MEC1") (pin "1") (pinfunction "2_1") (pintype "passive+no_connect"))
    )
    (net (code "43") (name "unconnected-(MEC2-2-Pad1)") (class "Default")
      (node (ref "MEC2") (pin "1") (pinfunction "2_1") (pintype "passive+no_connect"))
    )
    (net (code "44") (name "unconnected-(MEC3-2-Pad1)") (class "Default")
      (node (ref "MEC3") (pin "1") (pinfunction "2_1") (pintype "passive+no_connect"))
    )
    (net (code "45") (name "unconnected-(MEC4-2-Pad1)") (class "Default")
      (node (ref "MEC4") (pin "1") (pinfunction "2_1") (pintype "passive+no_connect"))
    )
    (net (code "46") (name "unconnected-(U1-NC-Pad1)") (class "Default")
      (node (ref "U1") (pin "1") (pinfunction "NC_1") (pintype "passive+no_connect"))
    )
    (net (code "47") (name "unconnected-(U10-DOUT-Pad2)") (class "Default")
      (node (ref "U10") (pin "2") (pinfunction "DOUT_2") (pintype "output+no_connect"))
    )
  )
)
